# telly_light.net
KiCad netlist of a schematic drawn in EAGLE
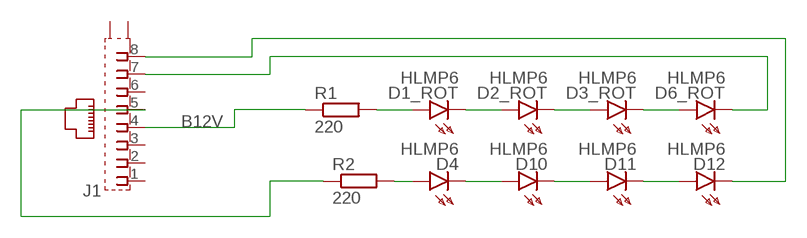
[diagram p0: schematic, sheet 1]
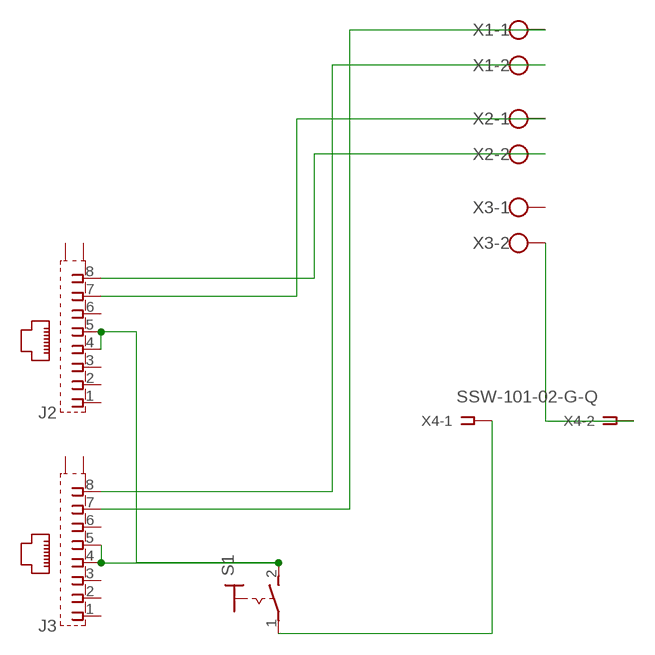
[diagram p1: schematic, sheet 2]

(export (version "E")
  (design (tool "Eeschema 10.0.6"))
  (components
    (comp (ref "D1_ROT")
      (value "HLMP6")
      (footprint "eagle-import:HLMP6")
      (fields (field (name "MF") "AGILENT TECHNOLOGIES") (field (name "MPN") "HLMP-6500"))
      (libsource (lib "eagle-import") (part "HLMP6"))
    )
    (comp (ref "D2_ROT")
      (value "HLMP6")
      (footprint "eagle-import:HLMP6")
      (fields (field (name "MF") "AGILENT TECHNOLOGIES") (field (name "MPN") "HLMP-6500"))
      (libsource (lib "eagle-import") (part "HLMP6"))
    )
    (comp (ref "D3_ROT")
      (value "HLMP6")
      (footprint "eagle-import:HLMP6")
      (fields (field (name "MF") "AGILENT TECHNOLOGIES") (field (name "MPN") "HLMP-6500"))
      (libsource (lib "eagle-import") (part "HLMP6"))
    )
    (comp (ref "D4")
      (value "HLMP6")
      (footprint "eagle-import:HLMP6")
      (fields (field (name "MF") "AGILENT TECHNOLOGIES") (field (name "MPN") "HLMP-6500"))
      (libsource (lib "eagle-import") (part "HLMP6"))
    )
    (comp (ref "D6_ROT")
      (value "HLMP6")
      (footprint "eagle-import:HLMP6")
      (fields (field (name "MF") "AGILENT TECHNOLOGIES") (field (name "MPN") "HLMP-6500"))
      (libsource (lib "eagle-import") (part "HLMP6"))
    )
    (comp (ref "D10")
      (value "HLMP6")
      (footprint "eagle-import:HLMP6")
      (fields (field (name "MF") "AGILENT TECHNOLOGIES") (field (name "MPN") "HLMP-6500"))
      (libsource (lib "eagle-import") (part "HLMP6"))
    )
    (comp (ref "D11")
      (value "HLMP6")
      (footprint "eagle-import:HLMP6")
      (fields (field (name "MF") "AGILENT TECHNOLOGIES") (field (name "MPN") "HLMP-6500"))
      (libsource (lib "eagle-import") (part "HLMP6"))
    )
    (comp (ref "D12")
      (value "HLMP6")
      (footprint "eagle-import:HLMP6")
      (fields (field (name "MF") "AGILENT TECHNOLOGIES") (field (name "MPN") "HLMP-6500"))
      (libsource (lib "eagle-import") (part "HLMP6"))
    )
    (comp (ref "J1")
      (value "555153-1")
      (footprint "eagle-import:555153-1")
      (libsource (lib "eagle-import") (part "555153-1"))
    )
    (comp (ref "R1")
      (value "220")
      (footprint "eagle-import:0204_7")
      (libsource (lib "eagle-import") (part "R-EU_0204/7"))
    )
    (comp (ref "R2")
      (value "220")
      (footprint "eagle-import:0204_7")
      (libsource (lib "eagle-import") (part "R-EU_0204/7"))
    )
    (comp (ref "J2")
      (value "555153-1")
      (footprint "eagle-import:555153-1")
      (libsource (lib "eagle-import") (part "555153-1"))
    )
    (comp (ref "J3")
      (value "555153-1")
      (footprint "eagle-import:555153-1")
      (libsource (lib "eagle-import") (part "555153-1"))
    )
    (comp (ref "S1")
      (value "MS243")
      (footprint "eagle-import:MS243")
      (libsource (lib "eagle-import") (part "MS243"))
    )
    (comp (ref "X1")
      (value "W237-102")
      (footprint "eagle-import:W237-102")
      (fields (field (name "MPN") "237-102"))
      (libsource (lib "eagle-import") (part "W237-102"))
    )
    (comp (ref "X2")
      (value "W237-102")
      (footprint "eagle-import:W237-102")
      (fields (field (name "MPN") "237-102"))
      (libsource (lib "eagle-import") (part "W237-102"))
    )
    (comp (ref "X3")
      (value "W237-102")
      (footprint "eagle-import:W237-102")
      (fields (field (name "MPN") "237-102"))
      (libsource (lib "eagle-import") (part "W237-102"))
    )
    (comp (ref "X4")
      (value "SSW-101-02-G-Q")
      (footprint "eagle-import:SSW-101-02-G-Q")
      (fields (field (name "MF") "Samtec Inc."))
      (libsource (lib "eagle-import") (part "SSW-101-02-G-Q"))
    )
  )
  (nets
    (net (code "1") (name "B12V") (class "Default")
      (node (ref "J1") (pin "5") (pinfunction "5_5") (pintype "passive"))
      (node (ref "R2") (pin "1") (pinfunction "1_1") (pintype "passive"))
    )
    (net (code "2") (name "Net-(D1_ROT-PadA)") (class "Default")
      (node (ref "D1_ROT") (pin "A") (pinfunction "A_A") (pintype "passive"))
      (node (ref "R1") (pin "2") (pinfunction "2_2") (pintype "passive"))
    )
    (net (code "3") (name "Net-(D1_ROT-PadK)") (class "Default")
      (node (ref "D1_ROT") (pin "K") (pinfunction "K_K") (pintype "passive"))
      (node (ref "D2_ROT") (pin "A") (pinfunction "A_A") (pintype "passive"))
    )
    (net (code "4") (name "Net-(D2_ROT-PadK)") (class "Default")
      (node (ref "D2_ROT") (pin "K") (pinfunction "K_K") (pintype "passive"))
      (node (ref "D3_ROT") (pin "A") (pinfunction "A_A") (pintype "passive"))
    )
    (net (code "5") (name "Net-(D3_ROT-PadK)") (class "Default")
      (node (ref "D3_ROT") (pin "K") (pinfunction "K_K") (pintype "passive"))
      (node (ref "D6_ROT") (pin "A") (pinfunction "A_A") (pintype "passive"))
    )
    (net (code "6") (name "Net-(D4-PadA)") (class "Default")
      (node (ref "D4") (pin "A") (pinfunction "A_A") (pintype "passive"))
      (node (ref "R2") (pin "2") (pinfunction "2_2") (pintype "passive"))
    )
    (net (code "7") (name "Net-(D6_ROT-PadK)") (class "Default")
      (node (ref "D6_ROT") (pin "K") (pinfunction "K_K") (pintype "passive"))
      (node (ref "J1") (pin "7") (pinfunction "7_7") (pintype "passive"))
    )
    (net (code "8") (name "Net-(D10-PadA)") (class "Default")
      (node (ref "D10") (pin "A") (pinfunction "A_A") (pintype "passive"))
      (node (ref "D4") (pin "K") (pinfunction "K_K") (pintype "passive"))
    )
    (net (code "9") (name "Net-(D10-PadK)") (class "Default")
      (node (ref "D10") (pin "K") (pinfunction "K_K") (pintype "passive"))
      (node (ref "D11") (pin "A") (pinfunction "A_A") (pintype "passive"))
    )
    (net (code "10") (name "Net-(D11-PadK)") (class "Default")
      (node (ref "D11") (pin "K") (pinfunction "K_K") (pintype "passive"))
      (node (ref "D12") (pin "A") (pinfunction "A_A") (pintype "passive"))
    )
    (net (code "11") (name "Net-(D12-PadK)") (class "Default")
      (node (ref "D12") (pin "K") (pinfunction "K_K") (pintype "passive"))
      (node (ref "J1") (pin "8") (pinfunction "8_8") (pintype "passive"))
    )
    (net (code "12") (name "Net-(J1-Pad4)") (class "Default")
      (node (ref "J1") (pin "4") (pinfunction "4_4") (pintype "passive"))
      (node (ref "R1") (pin "1") (pinfunction "1_1") (pintype "passive"))
    )
    (net (code "13") (name "Net-(S1-P)") (class "Default")
      (node (ref "S1") (pin "1") (pinfunction "P_1") (pintype "passive"))
      (node (ref "X4") (pin "1") (pinfunction "1_1") (pintype "passive"))
    )
    (net (code "14") (name "Net-(S1-S)") (class "Default")
      (node (ref "J2") (pin "4") (pinfunction "4_4") (pintype "passive"))
      (node (ref "J2") (pin "5") (pinfunction "5_5") (pintype "passive"))
      (node (ref "J3") (pin "4") (pinfunction "4_4") (pintype "passive"))
      (node (ref "J3") (pin "5") (pinfunction "5_5") (pintype "passive"))
      (node (ref "S1") (pin "2") (pinfunction "S_2") (pintype "passive"))
    )
    (net (code "15") (name "Net-(X1A-KL)") (class "Default")
      (node (ref "J3") (pin "7") (pinfunction "7_7") (pintype "passive"))
      (node (ref "X1") (pin "1") (pinfunction "KL_1") (pintype "passive"))
    )
    (net (code "16") (name "Net-(X1B-KL)") (class "Default")
      (node (ref "J3") (pin "8") (pinfunction "8_8") (pintype "passive"))
      (node (ref "X1") (pin "2") (pinfunction "KL_2") (pintype "passive"))
    )
    (net (code "17") (name "Net-(X2A-KL)") (class "Default")
      (node (ref "J2") (pin "7") (pinfunction "7_7") (pintype "passive"))
      (node (ref "X2") (pin "1") (pinfunction "KL_1") (pintype "passive"))
    )
    (net (code "18") (name "Net-(X2B-KL)") (class "Default")
      (node (ref "J2") (pin "8") (pinfunction "8_8") (pintype "passive"))
      (node (ref "X2") (pin "2") (pinfunction "KL_2") (pintype "passive"))
    )
    (net (code "19") (name "Net-(X3B-KL)") (class "Default")
      (node (ref "X3") (pin "2") (pinfunction "KL_2") (pintype "passive"))
      (node (ref "X4") (pin "2") (pinfunction "1_2") (pintype "passive"))
    )
    (net (code "20") (name "unconnected-(J1-Pad1)") (class "Default")
      (node (ref "J1") (pin "1") (pinfunction "1_1") (pintype "passive"))
    )
    (net (code "21") (name "unconnected-(J1-Pad2)") (class "Default")
      (node (ref "J1") (pin "2") (pinfunction "2_2") (pintype "passive"))
    )
    (net (code "22") (name "unconnected-(J1-Pad3)") (class "Default")
      (node (ref "J1") (pin "3") (pinfunction "3_3") (pintype "passive"))
    )
    (net (code "23") (name "unconnected-(J1-Pad6)") (class "Default")
      (node (ref "J1") (pin "6") (pinfunction "6_6") (pintype "passive"))
    )
    (net (code "24") (name "unconnected-(J1-S1-PadG1)") (class "Default")
      (node (ref "J1") (pin "G1") (pinfunction "S1_G1") (pintype "passive"))
    )
    (net (code "25") (name "unconnected-(J1-S2-PadG2)") (class "Default")
      (node (ref "J1") (pin "G2") (pinfunction "S2_G2") (pintype "passive"))
    )
    (net (code "26") (name "unconnected-(J2-Pad1)") (class "Default")
      (node (ref "J2") (pin "1") (pinfunction "1_1") (pintype "passive"))
    )
    (net (code "27") (name "unconnected-(J2-Pad2)") (class "Default")
      (node (ref "J2") (pin "2") (pinfunction "2_2") (pintype "passive"))
    )
    (net (code "28") (name "unconnected-(J2-Pad3)") (class "Default")
      (node (ref "J2") (pin "3") (pinfunction "3_3") (pintype "passive"))
    )
    (net (code "29") (name "unconnected-(J2-Pad6)") (class "Default")
      (node (ref "J2") (pin "6") (pinfunction "6_6") (pintype "passive"))
    )
    (net (code "30") (name "unconnected-(J2-S1-PadG1)") (class "Default")
      (node (ref "J2") (pin "G1") (pinfunction "S1_G1") (pintype "passive"))
    )
    (net (code "31") (name "unconnected-(J2-S2-PadG2)") (class "Default")
      (node (ref "J2") (pin "G2") (pinfunction "S2_G2") (pintype "passive"))
    )
    (net (code "32") (name "unconnected-(J3-Pad1)") (class "Default")
      (node (ref "J3") (pin "1") (pinfunction "1_1") (pintype "passive"))
    )
    (net (code "33") (name "unconnected-(J3-Pad2)") (class "Default")
      (node (ref "J3") (pin "2") (pinfunction "2_2") (pintype "passive"))
    )
    (net (code "34") (name "unconnected-(J3-Pad3)") (class "Default")
      (node (ref "J3") (pin "3") (pinfunction "3_3") (pintype "passive"))
    )
    (net (code "35") (name "unconnected-(J3-Pad6)") (class "Default")
      (node (ref "J3") (pin "6") (pinfunction "6_6") (pintype "passive"))
    )
    (net (code "36") (name "unconnected-(J3-S1-PadG1)") (class "Default")
      (node (ref "J3") (pin "G1") (pinfunction "S1_G1") (pintype "passive"))
    )
    (net (code "37") (name "unconnected-(J3-S2-PadG2)") (class "Default")
      (node (ref "J3") (pin "G2") (pinfunction "S2_G2") (pintype "passive"))
    )
    (net (code "38") (name "unconnected-(X3A-KL-Pad1)") (class "Default")
      (node (ref "X3") (pin "1") (pinfunction "KL_1") (pintype "passive"))
    )
  )
)
